# CUC.net
KiCad netlist of a schematic drawn in Altium Designer
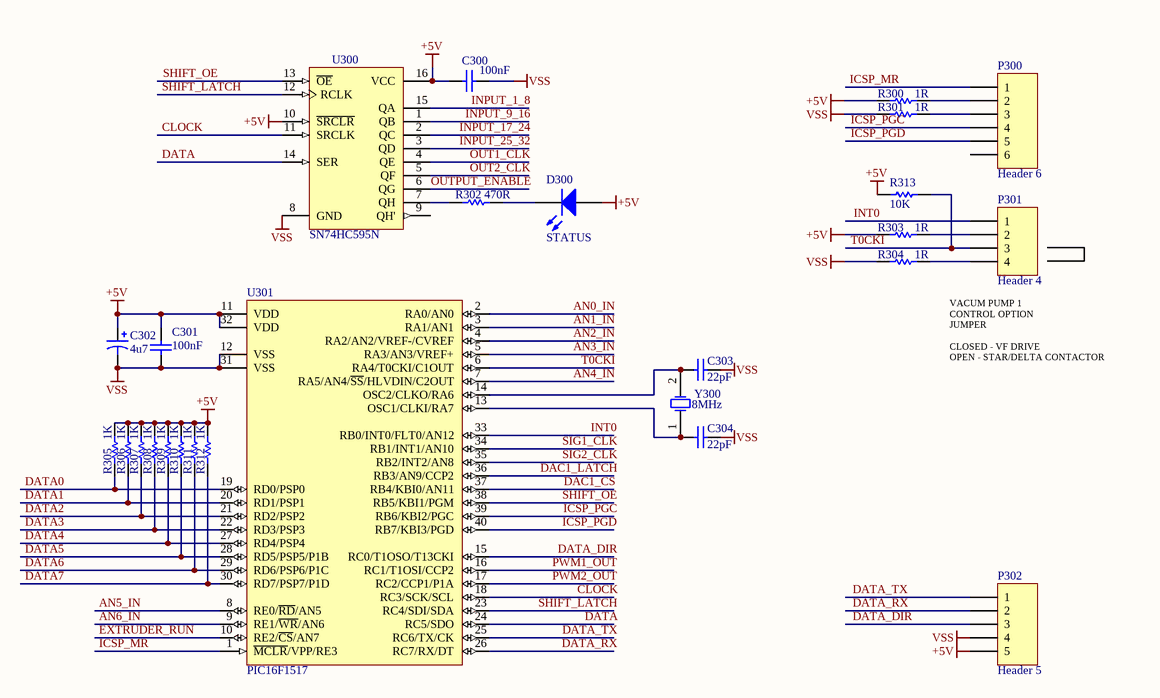
[diagram p0: CUC.SchDoc]

(export (version "E")
  (design (tool "Eeschema 10.0.6"))
  (components
    (comp (ref "C300")
      (value "100nF")
      (footprint "1206")
      (description "Ceramic Chip Capacitor - Standard")
      (fields (field (name "PUBLISHER") "Altium Limited"))
      (libsource (lib "KEMET Chip Capacitor") (part "C1206"))
    )
    (comp (ref "C301")
      (value "100nF")
      (footprint "1206")
      (description "Ceramic Chip Capacitor - Standard")
      (fields (field (name "PUBLISHER") "Altium Limited"))
      (libsource (lib "KEMET Chip Capacitor") (part "C1206"))
    )
    (comp (ref "C302")
      (value "4u7")
      (footprint "Vishay Electrolytic Radial-Lead Capacitor:94SP-C")
      (description "Solid Aluminum Capacitor with Organic Semiconductor Electrolyte: 100uF, 10V, Bulk Pack")
      (fields (field (name "PUBLISHER") "Altium Limited"))
      (libsource (lib "Vishay Electrolytic Radial-Lead Capacitor") (part "94SA107X0010EBP"))
    )
    (comp (ref "C303")
      (value "22pF")
      (footprint "0402")
      (description "Ceramic Chip Capacitor - Standard")
      (fields (field (name "PUBLISHER") "Altium Limited"))
      (libsource (lib "KEMET Chip Capacitor") (part "C0402"))
    )
    (comp (ref "C304")
      (value "22pF")
      (footprint "0402")
      (description "Ceramic Chip Capacitor - Standard")
      (fields (field (name "PUBLISHER") "Altium Limited"))
      (libsource (lib "KEMET Chip Capacitor") (part "C0402"))
    )
    (comp (ref "D300")
      (value "STATUS")
      (footprint "3.5X2.8X1.9")
      (description "Typical BLUE SiC LED")
      (fields (field (name "PUBLISHER") "Altium Limited"))
      (libsource (lib "Miscellaneous Devices") (part "LED3"))
    )
    (comp (ref "P300")
      (value "Header 6")
      (footprint "HDR1X6")
      (description "Header, 6-Pin")
      (fields (field (name "PUBLISHER") "Altium Limited"))
      (libsource (lib "Miscellaneous Connectors") (part "Header 6"))
    )
    (comp (ref "P301")
      (value "Header 4")
      (footprint "HDR1X4")
      (description "Header, 4-Pin")
      (fields (field (name "PUBLISHER") "Altium Limited"))
      (libsource (lib "Miscellaneous Connectors") (part "Header 4"))
    )
    (comp (ref "P302")
      (value "Header 5")
      (footprint "HDR1X5")
      (description "Header, 5-Pin")
      (fields (field (name "PUBLISHER") "Altium Limited"))
      (libsource (lib "Miscellaneous Connectors") (part "Header 5"))
    )
    (comp (ref "R300")
      (value "1R")
      (footprint "ERA-0805")
      (fields (field (name "PUBLISHER") "Altium Limited"))
      (libsource (lib "Panasonic Resistor") (part "ERA6Y"))
    )
    (comp (ref "R301")
      (value "1R")
      (footprint "ERA-0805")
      (fields (field (name "PUBLISHER") "Altium Limited"))
      (libsource (lib "Panasonic Resistor") (part "ERA6Y"))
    )
    (comp (ref "R302")
      (value "470R")
      (footprint "ERA-0805")
      (fields (field (name "PUBLISHER") "Altium Limited"))
      (libsource (lib "Panasonic Resistor") (part "ERA6Y"))
    )
    (comp (ref "R303")
      (value "1R")
      (footprint "ERA-0805")
      (fields (field (name "PUBLISHER") "Altium Limited"))
      (libsource (lib "Panasonic Resistor") (part "ERA6Y"))
    )
    (comp (ref "R304")
      (value "1R")
      (footprint "ERA-0805")
      (fields (field (name "PUBLISHER") "Altium Limited"))
      (libsource (lib "Panasonic Resistor") (part "ERA6Y"))
    )
    (comp (ref "R305")
      (value "1K")
      (footprint "ERA-0805")
      (fields (field (name "PUBLISHER") "Altium Limited"))
      (libsource (lib "Panasonic Resistor") (part "ERA6Y"))
    )
    (comp (ref "R306")
      (value "1K")
      (footprint "ERA-0805")
      (fields (field (name "PUBLISHER") "Altium Limited"))
      (libsource (lib "Panasonic Resistor") (part "ERA6Y"))
    )
    (comp (ref "R307")
      (value "1K")
      (footprint "ERA-0805")
      (fields (field (name "PUBLISHER") "Altium Limited"))
      (libsource (lib "Panasonic Resistor") (part "ERA6Y"))
    )
    (comp (ref "R308")
      (value "1K")
      (footprint "ERA-0805")
      (fields (field (name "PUBLISHER") "Altium Limited"))
      (libsource (lib "Panasonic Resistor") (part "ERA6Y"))
    )
    (comp (ref "R309")
      (value "1K")
      (footprint "ERA-0805")
      (fields (field (name "PUBLISHER") "Altium Limited"))
      (libsource (lib "Panasonic Resistor") (part "ERA6Y"))
    )
    (comp (ref "R310")
      (value "1K")
      (footprint "ERA-0805")
      (fields (field (name "PUBLISHER") "Altium Limited"))
      (libsource (lib "Panasonic Resistor") (part "ERA6Y"))
    )
    (comp (ref "R311")
      (value "1K")
      (footprint "ERA-0805")
      (fields (field (name "PUBLISHER") "Altium Limited"))
      (libsource (lib "Panasonic Resistor") (part "ERA6Y"))
    )
    (comp (ref "R312")
      (value "1K")
      (footprint "ERA-0805")
      (fields (field (name "PUBLISHER") "Altium Limited"))
      (libsource (lib "Panasonic Resistor") (part "ERA6Y"))
    )
    (comp (ref "R313")
      (value "10K")
      (footprint "ERA-0603")
      (fields (field (name "PUBLISHER") "Altium Limited"))
      (libsource (lib "Panasonic Resistor") (part "ERA3Y"))
    )
    (comp (ref "U300")
      (value "SN74HC595N")
      (footprint "N016")
      (description "8-Bit Shift Register with 3-State Output Registers")
      (fields (field (name "PUBLISHER") "Altium Limited"))
      (libsource (lib "TI Logic Register") (part "SN74HC595N"))
    )
    (comp (ref "U301")
      (value "PIC16F1517")
      (footprint "PDIP600-P40")
      (fields (field (name "PUBLISHER") "Altium Limited"))
      (libsource (lib "Microchip Microcontroller 8-Bit PIC18") (part "PIC18F4520-E/P"))
    )
    (comp (ref "Y300")
      (value "8MHz")
      (footprint "HC49/4H_SMX")
      (description "Surface Mount Quartz Crystal")
      (fields (field (name "PUBLISHER") "Altium Limited"))
      (libsource (lib "C-MAC Crystal Oscillator") (part "HC49/4H_SMX"))
    )
  )
  (nets
    (net (code "1") (name "+5V") (class "Default")
      (node (ref "C300") (pin "1") (pinfunction "1_1") (pintype "passive"))
      (node (ref "C301") (pin "2") (pinfunction "2_2") (pintype "passive"))
      (node (ref "C302") (pin "1") (pinfunction "1_1") (pintype "passive"))
      (node (ref "D300") (pin "1") (pinfunction "A_1") (pintype "passive"))
      (node (ref "P302") (pin "5") (pinfunction "5_5") (pintype "passive"))
      (node (ref "R300") (pin "1") (pinfunction "1_1") (pintype "passive"))
      (node (ref "R303") (pin "1") (pinfunction "1_1") (pintype "passive"))
      (node (ref "R305") (pin "2") (pinfunction "2_2") (pintype "passive"))
      (node (ref "R306") (pin "2") (pinfunction "2_2") (pintype "passive"))
      (node (ref "R307") (pin "2") (pinfunction "2_2") (pintype "passive"))
      (node (ref "R308") (pin "2") (pinfunction "2_2") (pintype "passive"))
      (node (ref "R309") (pin "2") (pinfunction "2_2") (pintype "passive"))
      (node (ref "R310") (pin "2") (pinfunction "2_2") (pintype "passive"))
      (node (ref "R311") (pin "2") (pinfunction "2_2") (pintype "passive"))
      (node (ref "R312") (pin "2") (pinfunction "2_2") (pintype "passive"))
      (node (ref "R313") (pin "2") (pinfunction "2_2") (pintype "passive"))
      (node (ref "U300") (pin "10") (pinfunction "~{SRCLR}_10") (pintype "input"))
      (node (ref "U300") (pin "16") (pinfunction "VCC_16") (pintype "power_in"))
      (node (ref "U301") (pin "11") (pinfunction "VDD_11") (pintype "power_in"))
      (node (ref "U301") (pin "32") (pinfunction "VDD_32") (pintype "power_in"))
    )
    (net (code "2") (name "/AN0_IN") (class "Default")
      (node (ref "U301") (pin "2") (pinfunction "RA0/AN0_2") (pintype "bidirectional"))
    )
    (net (code "3") (name "/AN1_IN") (class "Default")
      (node (ref "U301") (pin "3") (pinfunction "RA1/AN1_3") (pintype "bidirectional"))
    )
    (net (code "4") (name "/AN2_IN") (class "Default")
      (node (ref "U301") (pin "4") (pinfunction "RA2/AN2/VREF-/CVREF_4") (pintype "bidirectional"))
    )
    (net (code "5") (name "/AN3_IN") (class "Default")
      (node (ref "U301") (pin "5") (pinfunction "RA3/AN3/VREF+_5") (pintype "bidirectional"))
    )
    (net (code "6") (name "/AN4_IN") (class "Default")
      (node (ref "U301") (pin "7") (pinfunction "RA5/AN4/~{SS}/HLVDIN/C2OUT_7") (pintype "bidirectional"))
    )
    (net (code "7") (name "/AN5_IN") (class "Default")
      (node (ref "U301") (pin "8") (pinfunction "RE0/~{RD}/AN5_8") (pintype "bidirectional"))
    )
    (net (code "8") (name "/AN6_IN") (class "Default")
      (node (ref "U301") (pin "9") (pinfunction "RE1/~{WR}/AN6_9") (pintype "bidirectional"))
    )
    (net (code "9") (name "/CLOCK") (class "Default")
      (node (ref "U300") (pin "11") (pinfunction "SRCLK_11") (pintype "input"))
      (node (ref "U301") (pin "18") (pinfunction "RC3/SCK/SCL_18") (pintype "bidirectional"))
    )
    (net (code "10") (name "/DAC1_CS") (class "Default")
      (node (ref "U301") (pin "37") (pinfunction "RB4/KBI0/AN11_37") (pintype "bidirectional"))
    )
    (net (code "11") (name "/DAC1_LATCH") (class "Default")
      (node (ref "U301") (pin "36") (pinfunction "RB3/AN9/CCP2_36") (pintype "bidirectional"))
    )
    (net (code "12") (name "/DATA") (class "Default")
      (node (ref "U300") (pin "14") (pinfunction "SER_14") (pintype "input"))
      (node (ref "U301") (pin "24") (pinfunction "RC5/SDO_24") (pintype "bidirectional"))
    )
    (net (code "13") (name "/DATA0") (class "Default")
      (node (ref "R305") (pin "1") (pinfunction "1_1") (pintype "passive"))
      (node (ref "U301") (pin "19") (pinfunction "RD0/PSP0_19") (pintype "bidirectional"))
    )
    (net (code "14") (name "/DATA1") (class "Default")
      (node (ref "R306") (pin "1") (pinfunction "1_1") (pintype "passive"))
      (node (ref "U301") (pin "20") (pinfunction "RD1/PSP1_20") (pintype "bidirectional"))
    )
    (net (code "15") (name "/DATA2") (class "Default")
      (node (ref "R307") (pin "1") (pinfunction "1_1") (pintype "passive"))
      (node (ref "U301") (pin "21") (pinfunction "RD2/PSP2_21") (pintype "bidirectional"))
    )
    (net (code "16") (name "/DATA3") (class "Default")
      (node (ref "R308") (pin "1") (pinfunction "1_1") (pintype "passive"))
      (node (ref "U301") (pin "22") (pinfunction "RD3/PSP3_22") (pintype "bidirectional"))
    )
    (net (code "17") (name "/DATA4") (class "Default")
      (node (ref "R309") (pin "1") (pinfunction "1_1") (pintype "passive"))
      (node (ref "U301") (pin "27") (pinfunction "RD4/PSP4_27") (pintype "bidirectional"))
    )
    (net (code "18") (name "/DATA5") (class "Default")
      (node (ref "R310") (pin "1") (pinfunction "1_1") (pintype "passive"))
      (node (ref "U301") (pin "28") (pinfunction "RD5/PSP5/P1B_28") (pintype "bidirectional"))
    )
    (net (code "19") (name "/DATA6") (class "Default")
      (node (ref "R311") (pin "1") (pinfunction "1_1") (pintype "passive"))
      (node (ref "U301") (pin "29") (pinfunction "RD6/PSP6/P1C_29") (pintype "bidirectional"))
    )
    (net (code "20") (name "/DATA7") (class "Default")
      (node (ref "R312") (pin "1") (pinfunction "1_1") (pintype "passive"))
      (node (ref "U301") (pin "30") (pinfunction "RD7/PSP7/P1D_30") (pintype "bidirectional"))
    )
    (net (code "21") (name "/DATA_DIR") (class "Default")
      (node (ref "P302") (pin "3") (pinfunction "3_3") (pintype "passive"))
      (node (ref "U301") (pin "15") (pinfunction "RC0/T1OSO/T13CKI_15") (pintype "bidirectional"))
    )
    (net (code "22") (name "/DATA_RX") (class "Default")
      (node (ref "P302") (pin "2") (pinfunction "2_2") (pintype "passive"))
      (node (ref "U301") (pin "26") (pinfunction "RC7/RX/DT_26") (pintype "bidirectional"))
    )
    (net (code "23") (name "/DATA_TX") (class "Default")
      (node (ref "P302") (pin "1") (pinfunction "1_1") (pintype "passive"))
      (node (ref "U301") (pin "25") (pinfunction "RC6/TX/CK_25") (pintype "bidirectional"))
    )
    (net (code "24") (name "/EXTRUDER_RUN") (class "Default")
      (node (ref "U301") (pin "10") (pinfunction "RE2/~{CS}/AN7_10") (pintype "bidirectional"))
    )
    (net (code "25") (name "/ICSP_MR") (class "Default")
      (node (ref "P300") (pin "1") (pinfunction "1_1") (pintype "passive"))
      (node (ref "U301") (pin "1") (pinfunction "~{MCLR}/VPP/RE3_1") (pintype "input"))
    )
    (net (code "26") (name "/ICSP_PGC") (class "Default")
      (node (ref "P300") (pin "4") (pinfunction "4_4") (pintype "passive"))
      (node (ref "U301") (pin "39") (pinfunction "RB6/KBI2/PGC_39") (pintype "bidirectional"))
    )
    (net (code "27") (name "/ICSP_PGD") (class "Default")
      (node (ref "P300") (pin "5") (pinfunction "5_5") (pintype "passive"))
      (node (ref "U301") (pin "40") (pinfunction "RB7/KBI3/PGD_40") (pintype "bidirectional"))
    )
    (net (code "28") (name "/INPUT_1_8") (class "Default")
      (node (ref "U300") (pin "15") (pinfunction "QA_15") (pintype "tri_state"))
    )
    (net (code "29") (name "/INPUT_9_16") (class "Default")
      (node (ref "U300") (pin "1") (pinfunction "QB_1") (pintype "tri_state"))
    )
    (net (code "30") (name "/INPUT_17_24") (class "Default")
      (node (ref "U300") (pin "2") (pinfunction "QC_2") (pintype "tri_state"))
    )
    (net (code "31") (name "/INPUT_25_32") (class "Default")
      (node (ref "U300") (pin "3") (pinfunction "QD_3") (pintype "tri_state"))
    )
    (net (code "32") (name "/INT0") (class "Default")
      (node (ref "P301") (pin "1") (pinfunction "1_1") (pintype "passive"))
      (node (ref "U301") (pin "33") (pinfunction "RB0/INT0/FLT0/AN12_33") (pintype "bidirectional"))
    )
    (net (code "33") (name "/OUT1_CLK") (class "Default")
      (node (ref "U300") (pin "4") (pinfunction "QE_4") (pintype "tri_state"))
    )
    (net (code "34") (name "/OUT2_CLK") (class "Default")
      (node (ref "U300") (pin "5") (pinfunction "QF_5") (pintype "tri_state"))
    )
    (net (code "35") (name "/OUTPUT_ENABLE") (class "Default")
      (node (ref "U300") (pin "6") (pinfunction "QG_6") (pintype "tri_state"))
    )
    (net (code "36") (name "/PWM1_OUT") (class "Default")
      (node (ref "U301") (pin "16") (pinfunction "RC1/T1OSI/CCP2_16") (pintype "bidirectional"))
    )
    (net (code "37") (name "/PWM2_OUT") (class "Default")
      (node (ref "U301") (pin "17") (pinfunction "RC2/CCP1/P1A_17") (pintype "bidirectional"))
    )
    (net (code "38") (name "/SHIFT_LATCH") (class "Default")
      (node (ref "U300") (pin "12") (pinfunction "RCLK_12") (pintype "input"))
      (node (ref "U301") (pin "23") (pinfunction "RC4/SDI/SDA_23") (pintype "bidirectional"))
    )
    (net (code "39") (name "/SHIFT_OE") (class "Default")
      (node (ref "U300") (pin "13") (pinfunction "~{OE}_13") (pintype "input"))
      (node (ref "U301") (pin "38") (pinfunction "RB5/KBI1/PGM_38") (pintype "bidirectional"))
    )
    (net (code "40") (name "/SIG1_CLK") (class "Default")
      (node (ref "U301") (pin "34") (pinfunction "RB1/INT1/AN10_34") (pintype "bidirectional"))
    )
    (net (code "41") (name "/SIG2_CLK") (class "Default")
      (node (ref "U301") (pin "35") (pinfunction "RB2/INT2/AN8_35") (pintype "bidirectional"))
    )
    (net (code "42") (name "/T0CKI") (class "Default")
      (node (ref "P301") (pin "3") (pinfunction "3_3") (pintype "passive"))
      (node (ref "R313") (pin "1") (pinfunction "1_1") (pintype "passive"))
      (node (ref "U301") (pin "6") (pinfunction "RA4/T0CKI/C1OUT_6") (pintype "bidirectional"))
    )
    (net (code "43") (name "Net-(D300-K)") (class "Default")
      (node (ref "D300") (pin "2") (pinfunction "K_2") (pintype "passive"))
      (node (ref "R302") (pin "2") (pinfunction "2_2") (pintype "passive"))
    )
    (net (code "44") (name "Net-(P300-Pad2)") (class "Default")
      (node (ref "P300") (pin "2") (pinfunction "2_2") (pintype "passive"))
      (node (ref "R300") (pin "2") (pinfunction "2_2") (pintype "passive"))
    )
    (net (code "45") (name "Net-(P300-Pad3)") (class "Default")
      (node (ref "P300") (pin "3") (pinfunction "3_3") (pintype "passive"))
      (node (ref "R301") (pin "2") (pinfunction "2_2") (pintype "passive"))
    )
    (net (code "46") (name "Net-(P301-Pad2)") (class "Default")
      (node (ref "P301") (pin "2") (pinfunction "2_2") (pintype "passive"))
      (node (ref "R303") (pin "2") (pinfunction "2_2") (pintype "passive"))
    )
    (net (code "47") (name "Net-(P301-Pad4)") (class "Default")
      (node (ref "P301") (pin "4") (pinfunction "4_4") (pintype "passive"))
      (node (ref "R304") (pin "2") (pinfunction "2_2") (pintype "passive"))
    )
    (net (code "48") (name "Net-(U300-QH)") (class "Default")
      (node (ref "R302") (pin "1") (pinfunction "1_1") (pintype "passive"))
      (node (ref "U300") (pin "7") (pinfunction "QH_7") (pintype "tri_state"))
    )
    (net (code "49") (name "Net-(U301-OSC1{slash}CLKI{slash}RA7)") (class "Default")
      (node (ref "C304") (pin "2") (pinfunction "2_2") (pintype "passive"))
      (node (ref "U301") (pin "13") (pinfunction "OSC1/CLKI/RA7_13") (pintype "bidirectional"))
      (node (ref "Y300") (pin "1") (pinfunction "OSC1_1") (pintype "passive"))
    )
    (net (code "50") (name "Net-(U301-OSC2{slash}CLKO{slash}RA6)") (class "Default")
      (node (ref "C303") (pin "2") (pinfunction "2_2") (pintype "passive"))
      (node (ref "U301") (pin "14") (pinfunction "OSC2/CLKO/RA6_14") (pintype "bidirectional"))
      (node (ref "Y300") (pin "2") (pinfunction "OSC2_2") (pintype "passive"))
    )
    (net (code "51") (name "VSS") (class "Default")
      (node (ref "C300") (pin "2") (pinfunction "2_2") (pintype "passive"))
      (node (ref "C301") (pin "1") (pinfunction "1_1") (pintype "passive"))
      (node (ref "C302") (pin "2") (pinfunction "2_2") (pintype "passive"))
      (node (ref "C303") (pin "1") (pinfunction "1_1") (pintype "passive"))
      (node (ref "C304") (pin "1") (pinfunction "1_1") (pintype "passive"))
      (node (ref "P302") (pin "4") (pinfunction "4_4") (pintype "passive"))
      (node (ref "R301") (pin "1") (pinfunction "1_1") (pintype "passive"))
      (node (ref "R304") (pin "1") (pinfunction "1_1") (pintype "passive"))
      (node (ref "U300") (pin "8") (pinfunction "GND_8") (pintype "power_in"))
      (node (ref "U301") (pin "12") (pinfunction "VSS_12") (pintype "power_in"))
      (node (ref "U301") (pin "31") (pinfunction "VSS_31") (pintype "power_in"))
    )
    (net (code "52") (name "unconnected-(P300-Pad6)") (class "Default")
      (node (ref "P300") (pin "6") (pinfunction "6_6") (pintype "passive"))
    )
    (net (code "53") (name "unconnected-(U300-QH'-Pad9)") (class "Default")
      (node (ref "U300") (pin "9") (pinfunction "QH'_9") (pintype "output"))
    )
  )
)
